# Sheet2.net
KiCad netlist of a schematic drawn in Altium Designer
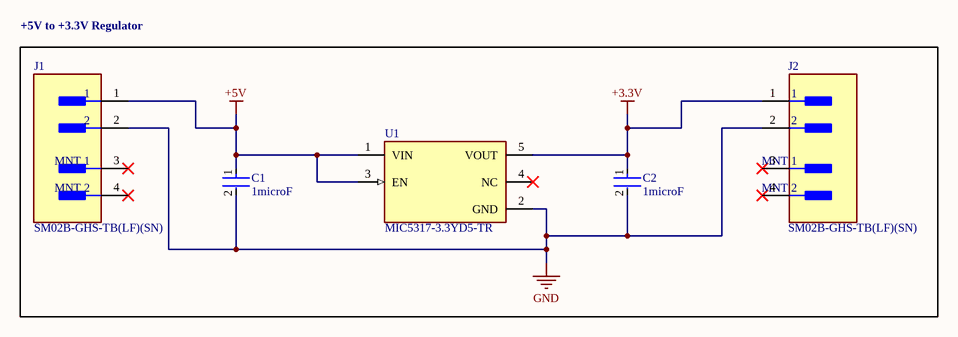
[diagram p0: Sheet2.SchDoc]

(export (version "E")
  (design (tool "Eeschema 10.0.6"))
  (components
    (comp (ref "C1")
      (value "1microF")
      (footprint "FP-CC0805-0_85-MFG")
      (description "CAP CER 1UF 10V X7R 0805")
      (fields
        (field (name "MANUFACTURER") "Yageo")
        (field (name "OCTOPART") "https://octopart.com/cc0805kkx7r6bb105-yageo-42522859")
      )
      (libsource (lib "Altium Content Vault") (part "11868f565c42a9108669ba33697ecf6"))
    )
    (comp (ref "C2")
      (value "1microF")
      (footprint "FP-CC0805-0_85-MFG")
      (description "CAP CER 1UF 10V X7R 0805")
      (fields
        (field (name "MANUFACTURER") "Yageo")
        (field (name "OCTOPART") "https://octopart.com/cc0805kkx7r6bb105-yageo-42522859")
      )
      (libsource (lib "Altium Content Vault") (part "11868f565c42a9108669ba33697ecf6"))
    )
    (comp (ref "J1")
      (value "SM02B-GHS-TB(LF)(SN)")
      (footprint "FP-SM02B-GHS-TB_LF_SN-MFG")
      (description "CONN HEADER SMD R/A 2POS 1.25MM")
      (libsource (lib "Altium Content Vault") (part "56ec3178a87b3978bdc1b3682cd516a"))
    )
    (comp (ref "J2")
      (value "SM02B-GHS-TB(LF)(SN)")
      (footprint "FP-SM02B-GHS-TB_LF_SN-MFG")
      (description "CONN HEADER SMD R/A 2POS 1.25MM")
      (libsource (lib "") (part "56ec3178a87b3978bdc1b3682cd516a_1"))
    )
    (comp (ref "U1")
      (value "MIC5317-3.3YD5-TR")
      (footprint "FP-C04-1179-MFG")
      (description "MIC5317-3.3YD5-TR LDO Regulator Pos 3.3V 0.15A 5-Pin TSOT-23 T/R")
      (libsource (lib "Altium Content Vault") (part "ffa7970afa5bd4475d63c28c55078a9"))
    )
  )
  (nets
    (net (code "1") (name "+3.3V") (class "Default")
      (node (ref "C2") (pin "1") (pinfunction "1_1") (pintype "passive"))
      (node (ref "J2") (pin "1") (pinfunction "1_1") (pintype "passive"))
      (node (ref "U1") (pin "5") (pinfunction "VOUT_5") (pintype "power_in"))
    )
    (net (code "2") (name "+5V") (class "Default")
      (node (ref "C1") (pin "1") (pinfunction "1_1") (pintype "passive"))
      (node (ref "J1") (pin "1") (pinfunction "1_1") (pintype "passive"))
      (node (ref "U1") (pin "1") (pinfunction "VIN_1") (pintype "power_in"))
      (node (ref "U1") (pin "3") (pinfunction "EN_3") (pintype "input"))
    )
    (net (code "3") (name "GND") (class "Default")
      (node (ref "C1") (pin "2") (pinfunction "2_2") (pintype "passive"))
      (node (ref "C2") (pin "2") (pinfunction "2_2") (pintype "passive"))
      (node (ref "J1") (pin "2") (pinfunction "2_2") (pintype "passive"))
      (node (ref "J2") (pin "2") (pinfunction "2_2") (pintype "passive"))
      (node (ref "U1") (pin "2") (pinfunction "GND_2") (pintype "power_in"))
    )
    (net (code "4") (name "unconnected-(J1-MNT_1-Pad3)") (class "Default")
      (node (ref "J1") (pin "3") (pinfunction "MNT_1_3") (pintype "passive+no_connect"))
    )
    (net (code "5") (name "unconnected-(J1-MNT_2-Pad4)") (class "Default")
      (node (ref "J1") (pin "4") (pinfunction "MNT_2_4") (pintype "passive+no_connect"))
    )
    (net (code "6") (name "unconnected-(J2-MNT_1-Pad3)") (class "Default")
      (node (ref "J2") (pin "3") (pinfunction "MNT_1_3") (pintype "passive+no_connect"))
    )
    (net (code "7") (name "unconnected-(J2-MNT_2-Pad4)") (class "Default")
      (node (ref "J2") (pin "4") (pinfunction "MNT_2_4") (pintype "passive+no_connect"))
    )
    (net (code "8") (name "unconnected-(U1-NC-Pad4)") (class "Default")
      (node (ref "U1") (pin "4") (pinfunction "NC_4") (pintype "passive+no_connect"))
    )
  )
)
